# optronik.net
KiCad netlist of a schematic drawn in EAGLE
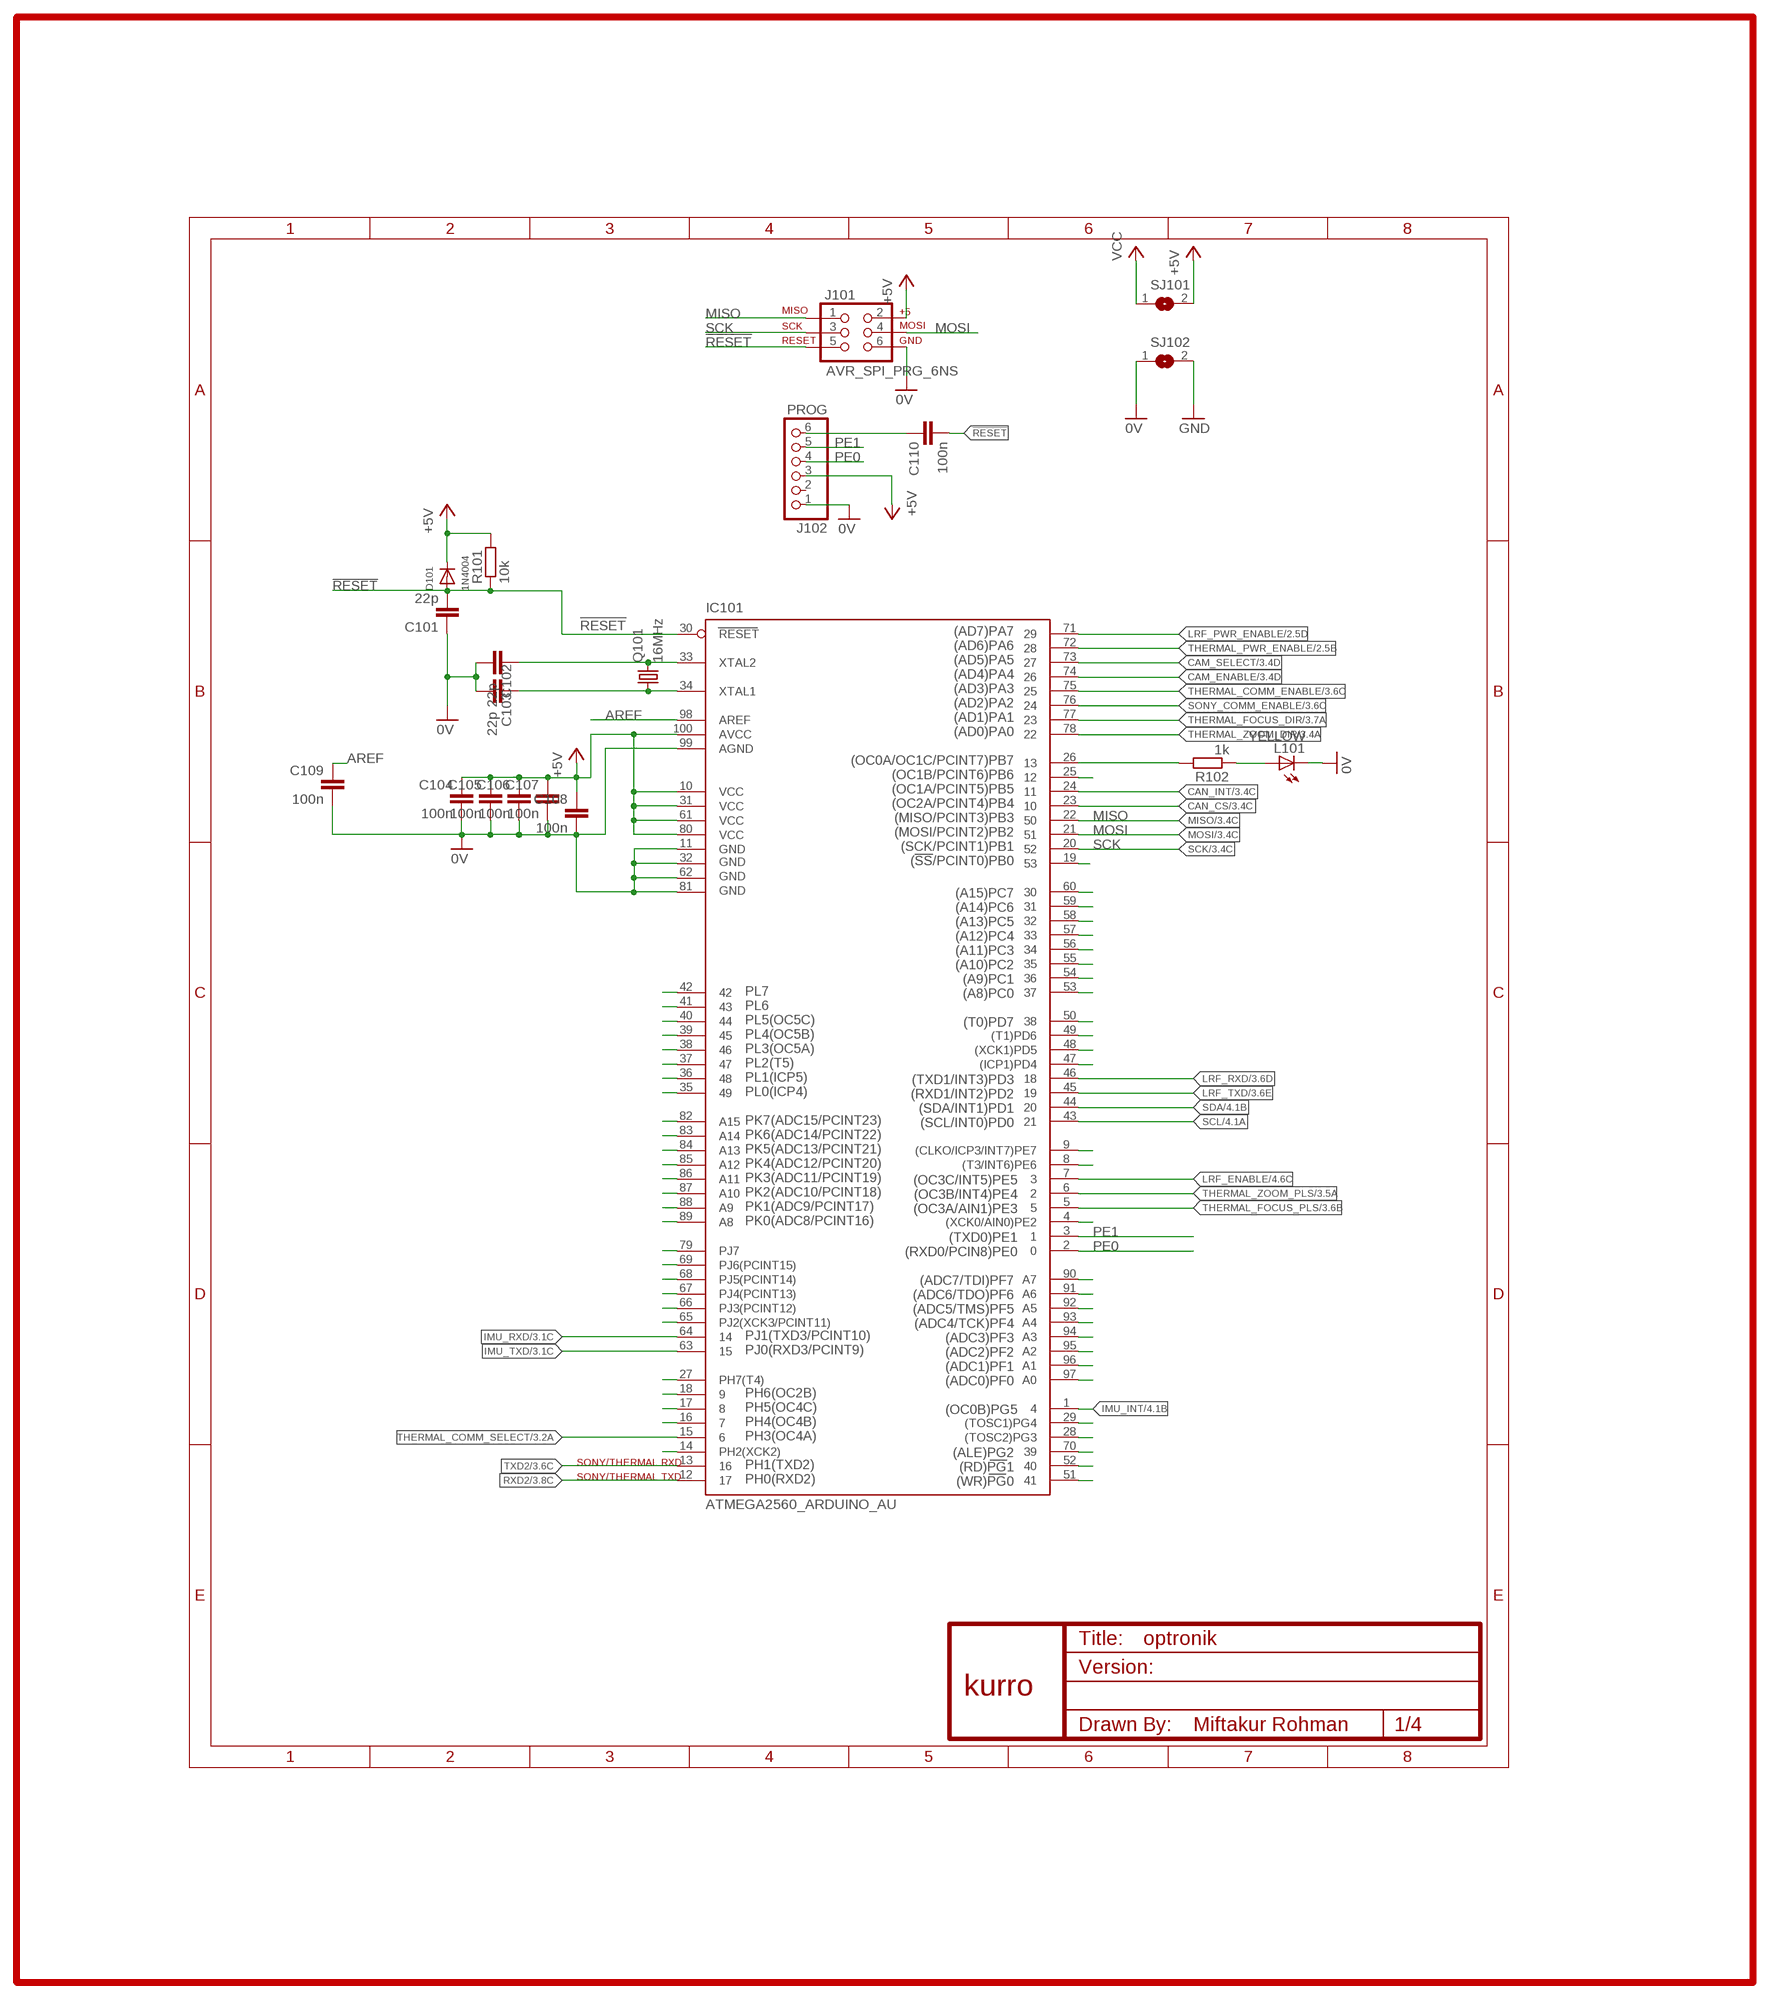
[diagram p0: schematic, sheet 1]
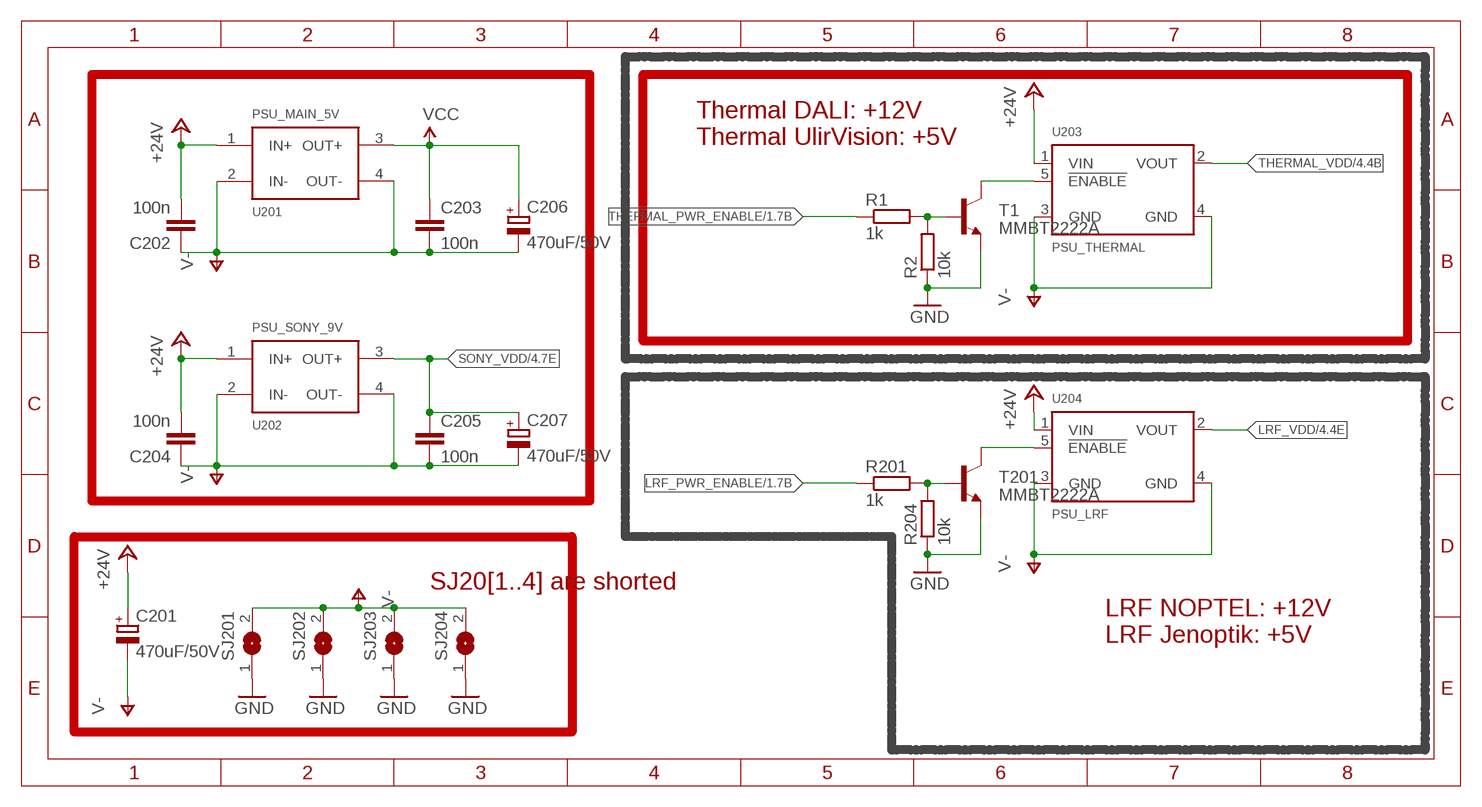
[diagram p1: schematic, sheet 2]
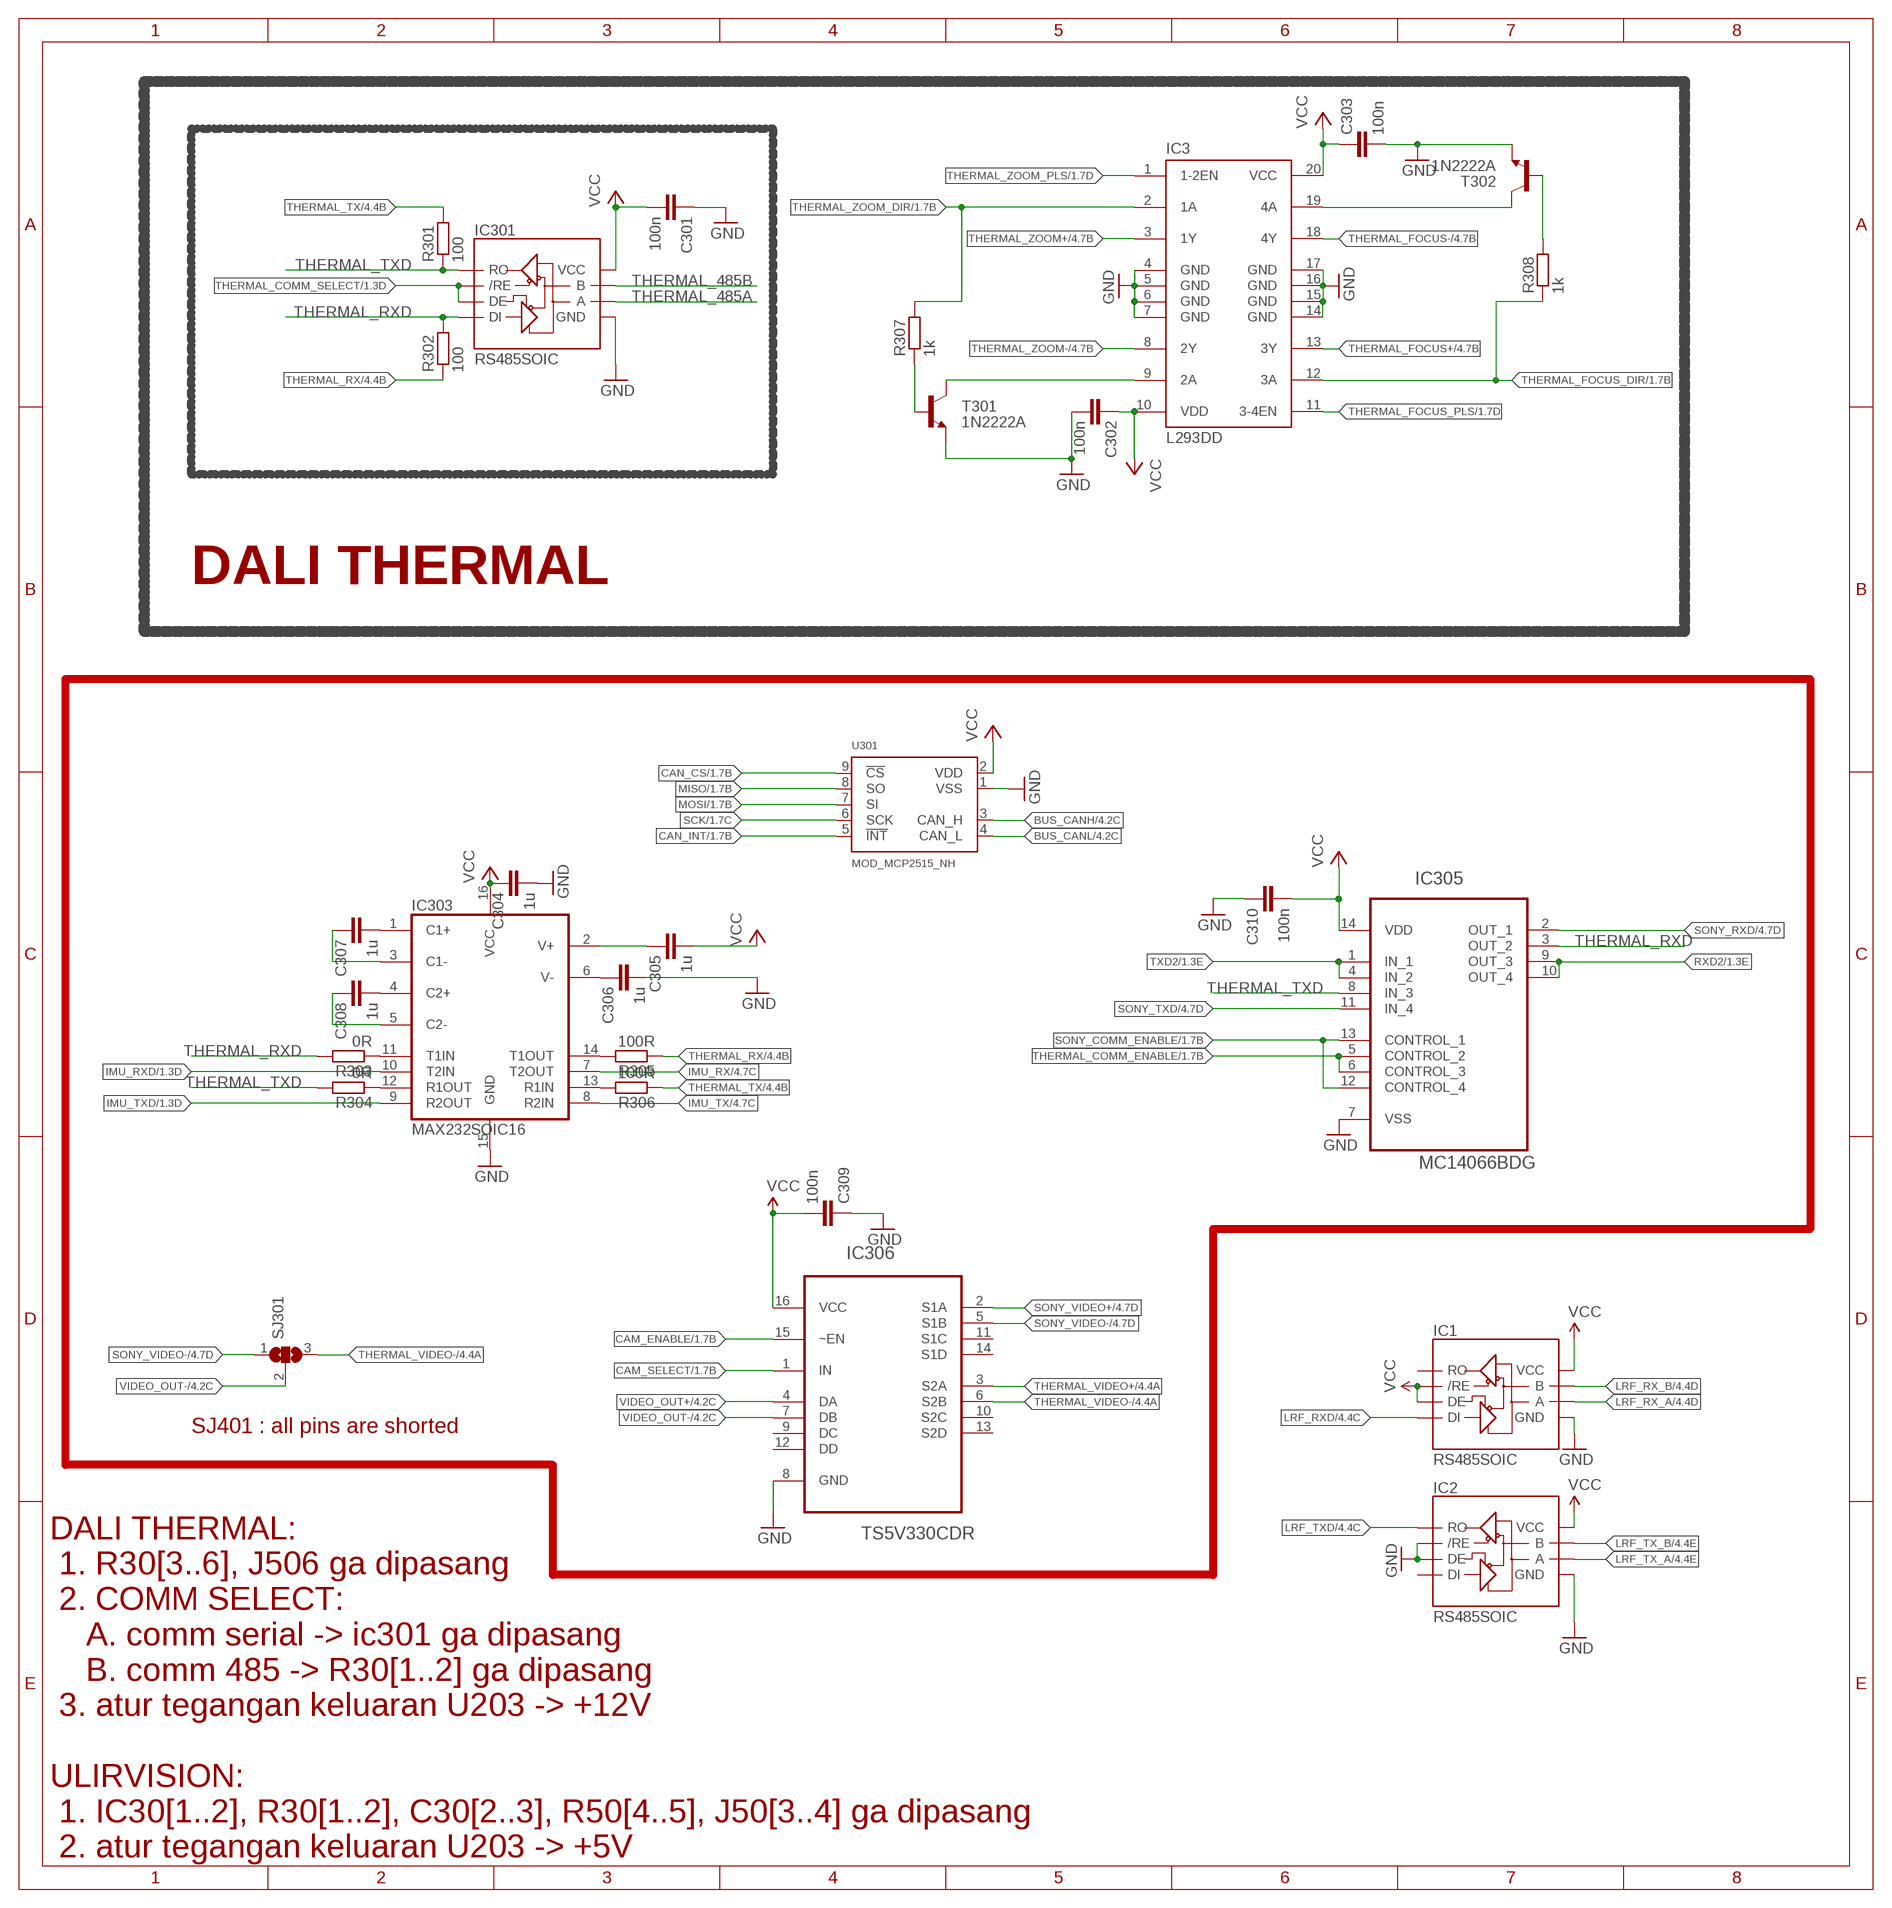
[diagram p2: schematic, sheet 3]
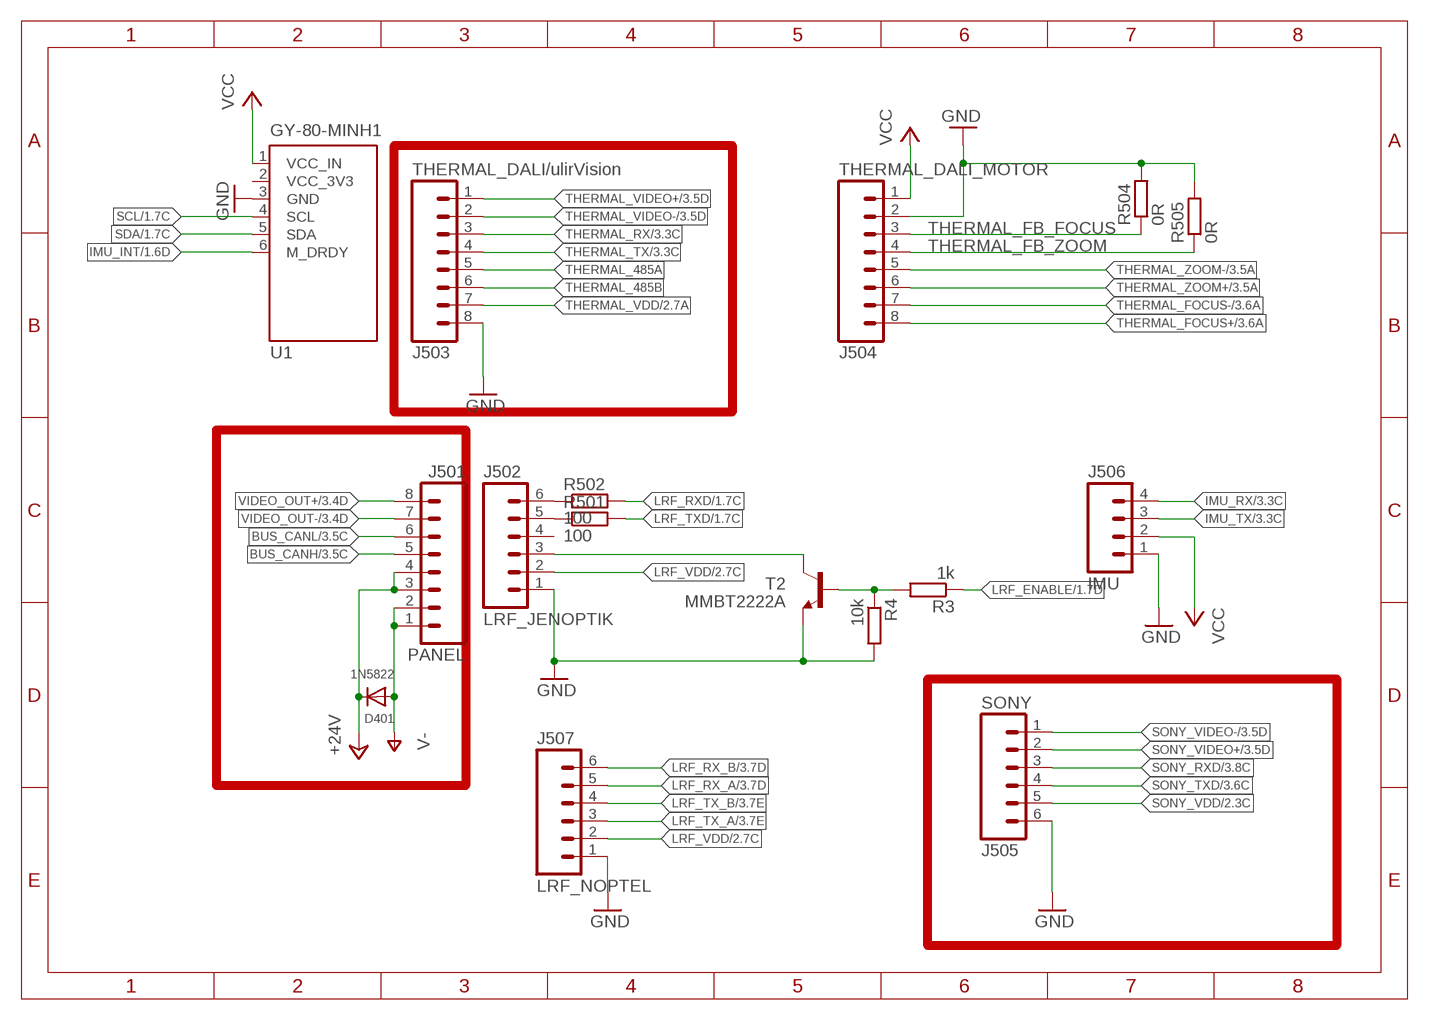
[diagram p3: schematic, sheet 4]

(export (version "E")
  (design (tool "Eeschema 10.0.6"))
  (components
    (comp (ref "D401")
      (value "1N5822")
      (footprint "eagle-import:SMADIODE")
      (libsource (lib "eagle-import") (part "DIODESMA"))
    )
    (comp (ref "J501")
      (value "PANEL")
      (footprint "eagle-import:XH-8-RA")
      (libsource (lib "eagle-import") (part "M08-XH-RA"))
    )
    (comp (ref "J502")
      (value "LRF_JENOPTIK")
      (footprint "eagle-import:XH-6-RA")
      (libsource (lib "eagle-import") (part "M06-XH-RA"))
    )
    (comp (ref "J503")
      (value "THERMAL_DALI/ulirVision")
      (footprint "eagle-import:XH-8-RA")
      (libsource (lib "eagle-import") (part "M08-XH-RA"))
    )
    (comp (ref "J504")
      (value "THERMAL_DALI_MOTOR")
      (footprint "eagle-import:XH-8-RA")
      (libsource (lib "eagle-import") (part "M08-XH-RA"))
    )
    (comp (ref "J505")
      (value "SONY")
      (footprint "eagle-import:XH-6-RA")
      (libsource (lib "eagle-import") (part "M06-XH-RA"))
    )
    (comp (ref "J506")
      (value "IMU")
      (footprint "eagle-import:XH-4-RA")
      (libsource (lib "eagle-import") (part "M04-XH-RA"))
    )
    (comp (ref "J507")
      (value "LRF_NOPTEL")
      (footprint "eagle-import:XH-6-RA")
      (libsource (lib "eagle-import") (part "M06-XH-RA"))
    )
    (comp (ref "R3")
      (value "1k")
      (footprint "eagle-import:R0603")
      (libsource (lib "eagle-import") (part "resistor_R-EU_R0603"))
    )
    (comp (ref "R4")
      (value "10k")
      (footprint "eagle-import:R0603")
      (libsource (lib "eagle-import") (part "resistor_R-EU_R0603"))
    )
    (comp (ref "R501")
      (value "100")
      (footprint "eagle-import:R0603")
      (libsource (lib "eagle-import") (part "R-EU_R0603"))
    )
    (comp (ref "R502")
      (value "100")
      (footprint "eagle-import:R0603")
      (libsource (lib "eagle-import") (part "R-EU_R0603"))
    )
    (comp (ref "R504")
      (value "0R")
      (footprint "eagle-import:R0603")
      (libsource (lib "eagle-import") (part "R-EU_R0603"))
    )
    (comp (ref "R505")
      (value "0R")
      (footprint "eagle-import:R0603")
      (libsource (lib "eagle-import") (part "R-EU_R0603"))
    )
    (comp (ref "T2")
      (value "MMBT2222A")
      (footprint "eagle-import:SOT23")
      (libsource (lib "eagle-import") (part "TRANSISTOR_NPNSOT23"))
    )
    (comp (ref "U1")
      (value "GY-80-MINH1")
      (footprint "eagle-import:GY-80-MINH1")
      (libsource (lib "eagle-import") (part "GY-80-MINH1"))
    )
    (comp (ref "C301")
      (value "100n")
      (footprint "eagle-import:C0603")
      (libsource (lib "eagle-import") (part "resistor_C-EUC0603"))
    )
    (comp (ref "C302")
      (value "100n")
      (footprint "eagle-import:C0603")
      (libsource (lib "eagle-import") (part "resistor_C-EUC0603"))
    )
    (comp (ref "C303")
      (value "100n")
      (footprint "eagle-import:C0603")
      (libsource (lib "eagle-import") (part "resistor_C-EUC0603"))
    )
    (comp (ref "C304")
      (value "1u")
      (footprint "eagle-import:C0603")
      (libsource (lib "eagle-import") (part "resistor_C-EUC0603"))
    )
    (comp (ref "C305")
      (value "1u")
      (footprint "eagle-import:C0603")
      (libsource (lib "eagle-import") (part "resistor_C-EUC0603"))
    )
    (comp (ref "C306")
      (value "1u")
      (footprint "eagle-import:C0603")
      (libsource (lib "eagle-import") (part "resistor_C-EUC0603"))
    )
    (comp (ref "C307")
      (value "1u")
      (footprint "eagle-import:C0603")
      (libsource (lib "eagle-import") (part "resistor_C-EUC0603"))
    )
    (comp (ref "C308")
      (value "1u")
      (footprint "eagle-import:C0603")
      (libsource (lib "eagle-import") (part "resistor_C-EUC0603"))
    )
    (comp (ref "C309")
      (value "100n")
      (footprint "eagle-import:C0603")
      (libsource (lib "eagle-import") (part "resistor_C-EUC0603"))
    )
    (comp (ref "C310")
      (value "100n")
      (footprint "eagle-import:C0603")
      (libsource (lib "eagle-import") (part "resistor_C-EUC0603"))
    )
    (comp (ref "IC1")
      (value "RS485SOIC")
      (footprint "eagle-import:SO08")
      (libsource (lib "eagle-import") (part "RS485SOIC"))
    )
    (comp (ref "IC2")
      (value "RS485SOIC")
      (footprint "eagle-import:SO08")
      (libsource (lib "eagle-import") (part "RS485SOIC"))
    )
    (comp (ref "IC3")
      (value "L293DD")
      (footprint "eagle-import:SO20W")
      (libsource (lib "eagle-import") (part "L293DD"))
    )
    (comp (ref "IC301")
      (value "RS485SOIC")
      (footprint "eagle-import:SO08")
      (libsource (lib "eagle-import") (part "RS485SOIC"))
    )
    (comp (ref "IC303")
      (value "MAX232SOIC16")
      (footprint "eagle-import:SO016")
      (libsource (lib "eagle-import") (part "MAX232SOIC16"))
    )
    (comp (ref "IC305")
      (value "MC14066BDG")
      (footprint "eagle-import:SOIC127P600X175-14N")
      (libsource (lib "eagle-import") (part "MC14066BDG"))
    )
    (comp (ref "IC306")
      (value "TS5V330CDR")
      (footprint "eagle-import:SOIC127P600X175-16N")
      (libsource (lib "eagle-import") (part "TS5V330CDR"))
    )
    (comp (ref "R301")
      (value "100")
      (footprint "eagle-import:R0603")
      (libsource (lib "eagle-import") (part "resistor_R-EU_R0603"))
    )
    (comp (ref "R302")
      (value "100")
      (footprint "eagle-import:R0603")
      (libsource (lib "eagle-import") (part "resistor_R-EU_R0603"))
    )
    (comp (ref "R303")
      (value "0R")
      (footprint "eagle-import:R0603")
      (libsource (lib "eagle-import") (part "resistor_R-EU_R0603"))
    )
    (comp (ref "R304")
      (value "0R")
      (footprint "eagle-import:R0603")
      (libsource (lib "eagle-import") (part "resistor_R-EU_R0603"))
    )
    (comp (ref "R305")
      (value "100R")
      (footprint "eagle-import:R0603")
      (libsource (lib "eagle-import") (part "resistor_R-EU_R0603"))
    )
    (comp (ref "R306")
      (value "100R")
      (footprint "eagle-import:R0603")
      (libsource (lib "eagle-import") (part "resistor_R-EU_R0603"))
    )
    (comp (ref "R307")
      (value "1k")
      (footprint "eagle-import:R0603")
      (libsource (lib "eagle-import") (part "resistor_R-EU_R0603"))
    )
    (comp (ref "R308")
      (value "1k")
      (footprint "eagle-import:R0603")
      (libsource (lib "eagle-import") (part "resistor_R-EU_R0603"))
    )
    (comp (ref "SJ301")
      (value "SJ2WS")
      (footprint "eagle-import:SJ_2S")
      (libsource (lib "eagle-import") (part "SJ2WS"))
    )
    (comp (ref "T301")
      (value "1N2222A")
      (footprint "eagle-import:SOT23")
      (libsource (lib "eagle-import") (part "TRANSISTOR_NPNSOT23"))
    )
    (comp (ref "T302")
      (value "1N2222A")
      (footprint "eagle-import:SOT23")
      (libsource (lib "eagle-import") (part "TRANSISTOR_NPNSOT23"))
    )
    (comp (ref "U301")
      (value "MOD_MCP2515_NH")
      (footprint "eagle-import:MCP2515_CAN2")
      (libsource (lib "eagle-import") (part "MOD_MCP2515_NH"))
    )
    (comp (ref "C201")
      (value "470uF/50V")
      (footprint "eagle-import:E3,5-10")
      (libsource (lib "eagle-import") (part "CPOL-EUE3.5-10"))
    )
    (comp (ref "C202")
      (value "100n")
      (footprint "eagle-import:C0603")
      (libsource (lib "eagle-import") (part "C-EUC0603"))
    )
    (comp (ref "C203")
      (value "100n")
      (footprint "eagle-import:C0603")
      (libsource (lib "eagle-import") (part "C-EUC0603"))
    )
    (comp (ref "C204")
      (value "100n")
      (footprint "eagle-import:C0603")
      (libsource (lib "eagle-import") (part "C-EUC0603"))
    )
    (comp (ref "C205")
      (value "100n")
      (footprint "eagle-import:C0603")
      (libsource (lib "eagle-import") (part "C-EUC0603"))
    )
    (comp (ref "C206")
      (value "470uF/50V")
      (footprint "eagle-import:E3,5-10")
      (libsource (lib "eagle-import") (part "CPOL-EUE3.5-10"))
    )
    (comp (ref "C207")
      (value "470uF/50V")
      (footprint "eagle-import:E3,5-10")
      (libsource (lib "eagle-import") (part "CPOL-EUE3.5-10"))
    )
    (comp (ref "R1")
      (value "1k")
      (footprint "eagle-import:R0603")
      (libsource (lib "eagle-import") (part "resistor_R-EU_R0603"))
    )
    (comp (ref "R2")
      (value "10k")
      (footprint "eagle-import:R0603")
      (libsource (lib "eagle-import") (part "resistor_R-EU_R0603"))
    )
    (comp (ref "R201")
      (value "1k")
      (footprint "eagle-import:R0603")
      (libsource (lib "eagle-import") (part "resistor_R-EU_R0603"))
    )
    (comp (ref "R204")
      (value "10k")
      (footprint "eagle-import:R0603")
      (libsource (lib "eagle-import") (part "resistor_R-EU_R0603"))
    )
    (comp (ref "SJ201")
      (value "SJS")
      (footprint "eagle-import:SJS")
      (libsource (lib "eagle-import") (part "SJS"))
    )
    (comp (ref "SJ202")
      (value "SJS")
      (footprint "eagle-import:SJS")
      (libsource (lib "eagle-import") (part "SJS"))
    )
    (comp (ref "SJ203")
      (value "SJS")
      (footprint "eagle-import:SJS")
      (libsource (lib "eagle-import") (part "SJS"))
    )
    (comp (ref "SJ204")
      (value "SJS")
      (footprint "eagle-import:SJS")
      (libsource (lib "eagle-import") (part "SJS"))
    )
    (comp (ref "T1")
      (value "MMBT2222A")
      (footprint "eagle-import:SOT23")
      (libsource (lib "eagle-import") (part "TRANSISTOR_NPNSOT23"))
    )
    (comp (ref "T201")
      (value "MMBT2222A")
      (footprint "eagle-import:SOT23")
      (libsource (lib "eagle-import") (part "TRANSISTOR_NPNSOT23"))
    )
    (comp (ref "U201")
      (value "PSU_MAIN_5V")
      (footprint "eagle-import:MP1584_MIN")
      (libsource (lib "eagle-import") (part "MP1584_MIN"))
    )
    (comp (ref "U202")
      (value "PSU_SONY_9V")
      (footprint "eagle-import:MP1584_MIN")
      (libsource (lib "eagle-import") (part "MP1584_MIN"))
    )
    (comp (ref "U203")
      (value "PSU_THERMAL")
      (footprint "eagle-import:MOD_LM2596")
      (libsource (lib "eagle-import") (part "MOD_LM2596"))
    )
    (comp (ref "U204")
      (value "PSU_LRF")
      (footprint "eagle-import:MOD_LM2596")
      (libsource (lib "eagle-import") (part "MOD_LM2596"))
    )
    (comp (ref "C101")
      (value "22p")
      (footprint "eagle-import:C0603")
      (libsource (lib "eagle-import") (part "C-EUC0603"))
    )
    (comp (ref "C102")
      (value "22p")
      (footprint "eagle-import:C0603")
      (libsource (lib "eagle-import") (part "C-EUC0603"))
    )
    (comp (ref "C103")
      (value "22p")
      (footprint "eagle-import:C0603")
      (libsource (lib "eagle-import") (part "C-EUC0603"))
    )
    (comp (ref "C104")
      (value "100n")
      (footprint "eagle-import:C0603")
      (libsource (lib "eagle-import") (part "C-EUC0603"))
    )
    (comp (ref "C105")
      (value "100n")
      (footprint "eagle-import:C0603")
      (libsource (lib "eagle-import") (part "C-EUC0603"))
    )
    (comp (ref "C106")
      (value "100n")
      (footprint "eagle-import:C0603")
      (libsource (lib "eagle-import") (part "C-EUC0603"))
    )
    (comp (ref "C107")
      (value "100n")
      (footprint "eagle-import:C0603")
      (libsource (lib "eagle-import") (part "C-EUC0603"))
    )
    (comp (ref "C108")
      (value "100n")
      (footprint "eagle-import:C0603")
      (libsource (lib "eagle-import") (part "C-EUC0603"))
    )
    (comp (ref "C109")
      (value "100n")
      (footprint "eagle-import:C0603")
      (libsource (lib "eagle-import") (part "C-EUC0603"))
    )
    (comp (ref "C110")
      (value "100n")
      (footprint "eagle-import:C0603")
      (libsource (lib "eagle-import") (part "C-EUC0603"))
    )
    (comp (ref "D101")
      (value "1N4004")
      (footprint "eagle-import:SOD-323F")
      (libsource (lib "eagle-import") (part "DIODESOD-323F"))
    )
    (comp (ref "IC101")
      (value "ATMEGA2560_ARDUINO_AU")
      (footprint "eagle-import:TQFP-100-14X14MM")
      (libsource (lib "eagle-import") (part "ATMEGA2560_ARDUINO_AU"))
    )
    (comp (ref "J101")
      (value "AVR_SPI_PRG_6NS")
      (footprint "eagle-import:2X3-NS")
      (libsource (lib "eagle-import") (part "AVR_SPI_PRG_6NS"))
    )
    (comp (ref "J102")
      (value "PROG")
      (footprint "eagle-import:1X06")
      (libsource (lib "eagle-import") (part "PINHD-1X6"))
    )
    (comp (ref "L101")
      (value "YELLOW")
      (footprint "eagle-import:LED5MM")
      (libsource (lib "eagle-import") (part "LED5MM"))
    )
    (comp (ref "Q101")
      (value "16MHz")
      (footprint "eagle-import:CRYSTAL-TXC-7A2")
      (libsource (lib "eagle-import") (part "CRYSTAL-TXC-7A2"))
    )
    (comp (ref "R101")
      (value "10k")
      (footprint "eagle-import:R0603")
      (libsource (lib "eagle-import") (part "resistor_R-EU_R0603"))
    )
    (comp (ref "R102")
      (value "1k")
      (footprint "eagle-import:R0603")
      (libsource (lib "eagle-import") (part "resistor_R-EU_R0603"))
    )
    (comp (ref "SJ101")
      (value "SJS")
      (footprint "eagle-import:SJS")
      (libsource (lib "eagle-import") (part "SJS"))
    )
    (comp (ref "SJ102")
      (value "SJS")
      (footprint "eagle-import:SJS")
      (libsource (lib "eagle-import") (part "SJS"))
    )
    (comp (ref "U$1")
      (value "KURRO_FOOTPRINT")
      (footprint "eagle-import:KURRO-LOGO")
      (libsource (lib "eagle-import") (part "KURRO_FOOTPRINT"))
    )
  )
  (nets
    (net (code "1") (name "+5V") (class "Default")
      (node (ref "C104") (pin "1") (pinfunction "1_1") (pintype "passive"))
      (node (ref "C105") (pin "1") (pinfunction "1_1") (pintype "passive"))
      (node (ref "C106") (pin "1") (pinfunction "1_1") (pintype "passive"))
      (node (ref "C107") (pin "1") (pinfunction "1_1") (pintype "passive"))
      (node (ref "C108") (pin "1") (pinfunction "1_1") (pintype "passive"))
      (node (ref "D101") (pin "C") (pinfunction "C_C") (pintype "passive"))
      (node (ref "IC101") (pin "10") (pinfunction "VCC_10") (pintype "power_in"))
      (node (ref "IC101") (pin "100") (pinfunction "AVCC_100") (pintype "power_in"))
      (node (ref "IC101") (pin "31") (pinfunction "VCC1_31") (pintype "power_in"))
      (node (ref "IC101") (pin "61") (pinfunction "VCC2_61") (pintype "power_in"))
      (node (ref "IC101") (pin "80") (pinfunction "VCC3_80") (pintype "power_in"))
      (node (ref "J101") (pin "2") (pinfunction "2_2") (pintype "passive"))
      (node (ref "J102") (pin "3") (pinfunction "3_3") (pintype "passive"))
      (node (ref "R101") (pin "2") (pinfunction "2_2") (pintype "passive"))
      (node (ref "SJ101") (pin "2") (pinfunction "2_2") (pintype "passive"))
    )
    (net (code "2") (name "+24V") (class "Default")
      (node (ref "C201") (pin "+") (pinfunction "+_+") (pintype "passive"))
      (node (ref "C202") (pin "2") (pinfunction "2_2") (pintype "passive"))
      (node (ref "C204") (pin "2") (pinfunction "2_2") (pintype "passive"))
      (node (ref "D401") (pin "C") (pinfunction "C_C") (pintype "passive"))
      (node (ref "J501") (pin "3") (pinfunction "3_3") (pintype "passive"))
      (node (ref "J501") (pin "4") (pinfunction "4_4") (pintype "passive"))
      (node (ref "U201") (pin "1") (pinfunction "IN+_1") (pintype "input"))
      (node (ref "U202") (pin "1") (pinfunction "IN+_1") (pintype "input"))
      (node (ref "U203") (pin "1") (pinfunction "VIN_1") (pintype "power_in"))
      (node (ref "U204") (pin "1") (pinfunction "VIN_1") (pintype "power_in"))
    )
    (net (code "3") (name "0V") (class "Default")
      (node (ref "C101") (pin "1") (pinfunction "1_1") (pintype "passive"))
      (node (ref "C102") (pin "1") (pinfunction "1_1") (pintype "passive"))
      (node (ref "C103") (pin "1") (pinfunction "1_1") (pintype "passive"))
      (node (ref "C104") (pin "2") (pinfunction "2_2") (pintype "passive"))
      (node (ref "C105") (pin "2") (pinfunction "2_2") (pintype "passive"))
      (node (ref "C106") (pin "2") (pinfunction "2_2") (pintype "passive"))
      (node (ref "C107") (pin "2") (pinfunction "2_2") (pintype "passive"))
      (node (ref "C108") (pin "2") (pinfunction "2_2") (pintype "passive"))
      (node (ref "C109") (pin "2") (pinfunction "2_2") (pintype "passive"))
      (node (ref "IC101") (pin "11") (pinfunction "GND_11") (pintype "power_in"))
      (node (ref "IC101") (pin "32") (pinfunction "GND1_32") (pintype "power_in"))
      (node (ref "IC101") (pin "62") (pinfunction "GND2_62") (pintype "power_in"))
      (node (ref "IC101") (pin "81") (pinfunction "GND3_81") (pintype "power_in"))
      (node (ref "IC101") (pin "99") (pinfunction "AGND_99") (pintype "power_in"))
      (node (ref "J101") (pin "6") (pinfunction "6_6") (pintype "passive"))
      (node (ref "J102") (pin "1") (pinfunction "1_1") (pintype "passive"))
      (node (ref "L101") (pin "K") (pinfunction "C_K") (pintype "passive"))
      (node (ref "SJ102") (pin "1") (pinfunction "1_1") (pintype "passive"))
    )
    (net (code "4") (name "AREF") (class "Default")
      (node (ref "C109") (pin "1") (pinfunction "1_1") (pintype "passive"))
      (node (ref "IC101") (pin "98") (pinfunction "AREF_98") (pintype "bidirectional"))
    )
    (net (code "5") (name "BUS_CANH") (class "Default")
      (node (ref "J501") (pin "5") (pinfunction "5_5") (pintype "passive"))
      (node (ref "U301") (pin "3") (pinfunction "CAN_H_3") (pintype "bidirectional"))
    )
    (net (code "6") (name "BUS_CANL") (class "Default")
      (node (ref "J501") (pin "6") (pinfunction "6_6") (pintype "passive"))
      (node (ref "U301") (pin "4") (pinfunction "CAN_L_4") (pintype "bidirectional"))
    )
    (net (code "7") (name "CAM_ENABLE") (class "Default")
      (node (ref "IC101") (pin "74") (pinfunction "26_74") (pintype "bidirectional"))
      (node (ref "IC306") (pin "15") (pinfunction "~{EN}_15") (pintype "input"))
    )
    (net (code "8") (name "CAM_SELECT") (class "Default")
      (node (ref "IC101") (pin "73") (pinfunction "27_73") (pintype "bidirectional"))
      (node (ref "IC306") (pin "1") (pinfunction "IN_1") (pintype "input"))
    )
    (net (code "9") (name "CAN_CS") (class "Default")
      (node (ref "IC101") (pin "23") (pinfunction "10_23") (pintype "bidirectional"))
      (node (ref "U301") (pin "9") (pinfunction "~{CS}_9") (pintype "bidirectional"))
    )
    (net (code "10") (name "CAN_INT") (class "Default")
      (node (ref "IC101") (pin "24") (pinfunction "11_24") (pintype "bidirectional"))
      (node (ref "U301") (pin "5") (pinfunction "~{INT}_5") (pintype "bidirectional"))
    )
    (net (code "11") (name "GND") (class "Default")
      (node (ref "C301") (pin "1") (pinfunction "1_1") (pintype "passive"))
      (node (ref "C302") (pin "2") (pinfunction "2_2") (pintype "passive"))
      (node (ref "C303") (pin "2") (pinfunction "2_2") (pintype "passive"))
      (node (ref "C304") (pin "2") (pinfunction "2_2") (pintype "passive"))
      (node (ref "C306") (pin "2") (pinfunction "2_2") (pintype "passive"))
      (node (ref "C309") (pin "1") (pinfunction "1_1") (pintype "passive"))
      (node (ref "C310") (pin "1") (pinfunction "1_1") (pintype "passive"))
      (node (ref "IC1") (pin "5") (pinfunction "GND_5") (pintype "bidirectional"))
      (node (ref "IC2") (pin "2") (pinfunction "/RE_2") (pintype "bidirectional"))
      (node (ref "IC2") (pin "3") (pinfunction "DE_3") (pintype "bidirectional"))
      (node (ref "IC2") (pin "5") (pinfunction "GND_5") (pintype "bidirectional"))
      (node (ref "IC3") (pin "14") (pinfunction "GND_14") (pintype "power_in"))
      (node (ref "IC3") (pin "15") (pinfunction "GND_15") (pintype "bidirectional"))
      (node (ref "IC3") (pin "16") (pinfunction "GND_16") (pintype "bidirectional"))
      (node (ref "IC3") (pin "17") (pinfunction "GND_17") (pintype "power_in"))
      (node (ref "IC3") (pin "4") (pinfunction "GND_4") (pintype "power_in"))
      (node (ref "IC3") (pin "5") (pinfunction "GND_5") (pintype "bidirectional"))
      (node (ref "IC3") (pin "6") (pinfunction "GND_6") (pintype "bidirectional"))
      (node (ref "IC3") (pin "7") (pinfunction "GND_7") (pintype "power_in"))
      (node (ref "IC301") (pin "5") (pinfunction "GND_5") (pintype "bidirectional"))
      (node (ref "IC303") (pin "15") (pinfunction "GND_15") (pintype "bidirectional"))
      (node (ref "IC305") (pin "7") (pinfunction "VSS_7") (pintype "passive"))
      (node (ref "IC306") (pin "8") (pinfunction "GND_8") (pintype "passive"))
      (node (ref "J502") (pin "1") (pinfunction "1_1") (pintype "passive"))
      (node (ref "J503") (pin "8") (pinfunction "8_8") (pintype "passive"))
      (node (ref "J504") (pin "2") (pinfunction "2_2") (pintype "passive"))
      (node (ref "J505") (pin "6") (pinfunction "6_6") (pintype "passive"))
      (node (ref "J506") (pin "1") (pinfunction "1_1") (pintype "passive"))
      (node (ref "J507") (pin "1") (pinfunction "1_1") (pintype "passive"))
      (node (ref "R2") (pin "1") (pinfunction "1_1") (pintype "passive"))
      (node (ref "R204") (pin "1") (pinfunction "1_1") (pintype "passive"))
      (node (ref "R4") (pin "2") (pinfunction "2_2") (pintype "passive"))
      (node (ref "R504") (pin "2") (pinfunction "2_2") (pintype "passive"))
      (node (ref "R505") (pin "2") (pinfunction "2_2") (pintype "passive"))
      (node (ref "SJ102") (pin "2") (pinfunction "2_2") (pintype "passive"))
      (node (ref "SJ201") (pin "1") (pinfunction "1_1") (pintype "passive"))
      (node (ref "SJ202") (pin "1") (pinfunction "1_1") (pintype "passive"))
      (node (ref "SJ203") (pin "1") (pinfunction "1_1") (pintype "passive"))
      (node (ref "SJ204") (pin "1") (pinfunction "1_1") (pintype "passive"))
      (node (ref "T1") (pin "2") (pinfunction "E_2") (pintype "passive"))
      (node (ref "T2") (pin "2") (pinfunction "E_2") (pintype "passive"))
      (node (ref "T201") (pin "2") (pinfunction "E_2") (pintype "passive"))
      (node (ref "T301") (pin "2") (pinfunction "E_2") (pintype "passive"))
      (node (ref "T302") (pin "2") (pinfunction "E_2") (pintype "passive"))
      (node (ref "U1") (pin "3") (pinfunction "GND_3") (pintype "bidirectional"))
      (node (ref "U301") (pin "1") (pinfunction "VSS_1") (pintype "bidirectional"))
    )
    (net (code "12") (name "IMU_INT") (class "Default")
      (node (ref "IC101") (pin "1") (pinfunction "4_1") (pintype "bidirectional"))
      (node (ref "U1") (pin "6") (pinfunction "M_DRDY_6") (pintype "bidirectional"))
    )
    (net (code "13") (name "IMU_RX") (class "Default")
      (node (ref "IC303") (pin "7") (pinfunction "T2OUT_7") (pintype "output"))
      (node (ref "J506") (pin "4") (pinfunction "4_4") (pintype "passive"))
    )
    (net (code "14") (name "IMU_RXD") (class "Default")
      (node (ref "IC101") (pin "64") (pinfunction "14_64") (pintype "bidirectional"))
      (node (ref "IC303") (pin "10") (pinfunction "T2IN_10") (pintype "input"))
    )
    (net (code "15") (name "IMU_TX") (class "Default")
      (node (ref "IC303") (pin "8") (pinfunction "R2IN_8") (pintype "input"))
      (node (ref "J506") (pin "3") (pinfunction "3_3") (pintype "passive"))
    )
    (net (code "16") (name "IMU_TXD") (class "Default")
      (node (ref "IC101") (pin "63") (pinfunction "15_63") (pintype "bidirectional"))
      (node (ref "IC303") (pin "9") (pinfunction "R2OUT_9") (pintype "output"))
    )
    (net (code "17") (name "LRF_ENABLE") (class "Default")
      (node (ref "IC101") (pin "7") (pinfunction "3_7") (pintype "bidirectional"))
      (node (ref "R3") (pin "1") (pinfunction "1_1") (pintype "passive"))
    )
    (net (code "18") (name "LRF_PWR_ENABLE") (class "Default")
      (node (ref "IC101") (pin "71") (pinfunction "29_71") (pintype "bidirectional"))
      (node (ref "R201") (pin "1") (pinfunction "1_1") (pintype "passive"))
    )
    (net (code "19") (name "LRF_RXD") (class "Default")
      (node (ref "IC1") (pin "4") (pinfunction "DI_4") (pintype "bidirectional"))
      (node (ref "IC101") (pin "46") (pinfunction "18_46") (pintype "bidirectional"))
      (node (ref "R502") (pin "2") (pinfunction "2_2") (pintype "passive"))
    )
    (net (code "20") (name "LRF_RX_A") (class "Default")
      (node (ref "IC1") (pin "6") (pinfunction "A_6") (pintype "bidirectional"))
      (node (ref "J507") (pin "5") (pinfunction "5_5") (pintype "passive"))
    )
    (net (code "21") (name "LRF_RX_B") (class "Default")
      (node (ref "IC1") (pin "7") (pinfunction "B_7") (pintype "bidirectional"))
      (node (ref "J507") (pin "6") (pinfunction "6_6") (pintype "passive"))
    )
    (net (code "22") (name "LRF_TXD") (class "Default")
      (node (ref "IC101") (pin "45") (pinfunction "19_45") (pintype "bidirectional"))
      (node (ref "IC2") (pin "1") (pinfunction "RO_1") (pintype "bidirectional"))
      (node (ref "R501") (pin "2") (pinfunction "2_2") (pintype "passive"))
    )
    (net (code "23") (name "LRF_TX_A") (class "Default")
      (node (ref "IC2") (pin "6") (pinfunction "A_6") (pintype "bidirectional"))
      (node (ref "J507") (pin "3") (pinfunction "3_3") (pintype "passive"))
    )
    (net (code "24") (name "LRF_TX_B") (class "Default")
      (node (ref "IC2") (pin "7") (pinfunction "B_7") (pintype "bidirectional"))
      (node (ref "J507") (pin "4") (pinfunction "4_4") (pintype "passive"))
    )
    (net (code "25") (name "LRF_VDD") (class "Default")
      (node (ref "J502") (pin "2") (pinfunction "2_2") (pintype "passive"))
      (node (ref "J507") (pin "2") (pinfunction "2_2") (pintype "passive"))
      (node (ref "U204") (pin "2") (pinfunction "VOUT_2") (pintype "output"))
    )
    (net (code "26") (name "MISO") (class "Default")
      (node (ref "IC101") (pin "22") (pinfunction "50_22") (pintype "bidirectional"))
      (node (ref "J101") (pin "1") (pinfunction "1_1") (pintype "passive"))
      (node (ref "U301") (pin "8") (pinfunction "SO_8") (pintype "bidirectional"))
    )
    (net (code "27") (name "MOSI") (class "Default")
      (node (ref "IC101") (pin "21") (pinfunction "51_21") (pintype "bidirectional"))
      (node (ref "J101") (pin "4") (pinfunction "4_4") (pintype "passive"))
      (node (ref "U301") (pin "7") (pinfunction "SI_7") (pintype "bidirectional"))
    )
    (net (code "28") (name "Net-(C110-Pad1)") (class "Default")
      (node (ref "C110") (pin "1") (pinfunction "1_1") (pintype "passive"))
      (node (ref "J102") (pin "6") (pinfunction "6_6") (pintype "passive"))
    )
    (net (code "29") (name "Net-(IC3-2A)") (class "Default")
      (node (ref "IC3") (pin "9") (pinfunction "2A_9") (pintype "input"))
      (node (ref "T301") (pin "3") (pinfunction "C_3") (pintype "passive"))
    )
    (net (code "30") (name "Net-(IC3-4A)") (class "Default")
      (node (ref "IC3") (pin "19") (pinfunction "4A_19") (pintype "input"))
      (node (ref "T302") (pin "3") (pinfunction "C_3") (pintype "passive"))
    )
    (net (code "31") (name "Net-(IC101-13)") (class "Default")
      (node (ref "IC101") (pin "26") (pinfunction "13_26") (pintype "bidirectional"))
      (node (ref "R102") (pin "2") (pinfunction "2_2") (pintype "passive"))
    )
    (net (code "32") (name "Net-(IC101-XTAL1)") (class "Default")
      (node (ref "C103") (pin "2") (pinfunction "2_2") (pintype "passive"))
      (node (ref "IC101") (pin "34") (pinfunction "XTAL1_34") (pintype "input"))
      (node (ref "Q101") (pin "P$1") (pinfunction "1_P$1") (pintype "passive"))
    )
    (net (code "33") (name "Net-(IC101-XTAL2)") (class "Default")
      (node (ref "C102") (pin "2") (pinfunction "2_2") (pintype "passive"))
      (node (ref "IC101") (pin "33") (pinfunction "XTAL2_33") (pintype "output"))
      (node (ref "Q101") (pin "P$2") (pinfunction "2_P$2") (pintype "passive"))
    )
    (net (code "34") (name "Net-(IC303-C1+)") (class "Default")
      (node (ref "C307") (pin "2") (pinfunction "2_2") (pintype "passive"))
      (node (ref "IC303") (pin "1") (pinfunction "C1+_1") (pintype "bidirectional"))
    )
    (net (code "35") (name "Net-(IC303-C1-)") (class "Default")
      (node (ref "C307") (pin "1") (pinfunction "1_1") (pintype "passive"))
      (node (ref "IC303") (pin "3") (pinfunction "C1-_3") (pintype "bidirectional"))
    )
    (net (code "36") (name "Net-(IC303-C2+)") (class "Default")
      (node (ref "C308") (pin "2") (pinfunction "2_2") (pintype "passive"))
      (node (ref "IC303") (pin "4") (pinfunction "C2+_4") (pintype "bidirectional"))
    )
    (net (code "37") (name "Net-(IC303-C2-)") (class "Default")
      (node (ref "C308") (pin "1") (pinfunction "1_1") (pintype "passive"))
      (node (ref "IC303") (pin "5") (pinfunction "C2-_5") (pintype "bidirectional"))
    )
    (net (code "38") (name "Net-(IC303-R1IN)") (class "Default")
      (node (ref "IC303") (pin "13") (pinfunction "R1IN_13") (pintype "input"))
      (node (ref "R306") (pin "2") (pinfunction "2_2") (pintype "passive"))
    )
    (net (code "39") (name "Net-(IC303-R1OUT)") (class "Default")
      (node (ref "IC303") (pin "12") (pinfunction "R1OUT_12") (pintype "output"))
      (node (ref "R304") (pin "1") (pinfunction "1_1") (pintype "passive"))
    )
    (net (code "40") (name "Net-(IC303-T1IN)") (class "Default")
      (node (ref "IC303") (pin "11") (pinfunction "T1IN_11") (pintype "input"))
      (node (ref "R303") (pin "1") (pinfunction "1_1") (pintype "passive"))
    )
    (net (code "41") (name "Net-(IC303-T1OUT)") (class "Default")
      (node (ref "IC303") (pin "14") (pinfunction "T1OUT_14") (pintype "output"))
      (node (ref "R305") (pin "2") (pinfunction "2_2") (pintype "passive"))
    )
    (net (code "42") (name "Net-(IC303-V+)") (class "Default")
      (node (ref "C305") (pin "1") (pinfunction "1_1") (pintype "passive"))
      (node (ref "IC303") (pin "2") (pinfunction "V+_2") (pintype "bidirectional"))
    )
    (net (code "43") (name "Net-(IC303-V-)") (class "Default")
      (node (ref "C306") (pin "1") (pinfunction "1_1") (pintype "passive"))
      (node (ref "IC303") (pin "6") (pinfunction "V-_6") (pintype "bidirectional"))
    )
    (net (code "44") (name "Net-(J502-Pad5)") (class "Default")
      (node (ref "J502") (pin "5") (pinfunction "5_5") (pintype "passive"))
      (node (ref "R501") (pin "1") (pinfunction "1_1") (pintype "passive"))
    )
    (net (code "45") (name "Net-(J502-Pad6)") (class "Default")
      (node (ref "J502") (pin "6") (pinfunction "6_6") (pintype "passive"))
      (node (ref "R502") (pin "1") (pinfunction "1_1") (pintype "passive"))
    )
    (net (code "46") (name "Net-(L101-PadA)") (class "Default")
      (node (ref "L101") (pin "A") (pinfunction "A_A") (pintype "passive"))
      (node (ref "R102") (pin "1") (pinfunction "1_1") (pintype "passive"))
    )
    (net (code "47") (name "Net-(T1-B)") (class "Default")
      (node (ref "R1") (pin "2") (pinfunction "2_2") (pintype "passive"))
      (node (ref "R2") (pin "2") (pinfunction "2_2") (pintype "passive"))
      (node (ref "T1") (pin "1") (pinfunction "B_1") (pintype "passive"))
    )
    (net (code "48") (name "Net-(T1-C)") (class "Default")
      (node (ref "T1") (pin "3") (pinfunction "C_3") (pintype "passive"))
      (node (ref "U203") (pin "5") (pinfunction "~{ENABLE}_5") (pintype "input"))
    )
    (net (code "49") (name "Net-(T2-B)") (class "Default")
      (node (ref "R3") (pin "2") (pinfunction "2_2") (pintype "passive"))
      (node (ref "R4") (pin "1") (pinfunction "1_1") (pintype "passive"))
      (node (ref "T2") (pin "1") (pinfunction "B_1") (pintype "passive"))
    )
    (net (code "50") (name "Net-(T2-C)") (class "Default")
      (node (ref "J502") (pin "3") (pinfunction "3_3") (pintype "passive"))
      (node (ref "T2") (pin "3") (pinfunction "C_3") (pintype "passive"))
    )
    (net (code "51") (name "Net-(T201-B)") (class "Default")
      (node (ref "R201") (pin "2") (pinfunction "2_2") (pintype "passive"))
      (node (ref "R204") (pin "2") (pinfunction "2_2") (pintype "passive"))
      (node (ref "T201") (pin "1") (pinfunction "B_1") (pintype "passive"))
    )
    (net (code "52") (name "Net-(T201-C)") (class "Default")
      (node (ref "T201") (pin "3") (pinfunction "C_3") (pintype "passive"))
      (node (ref "U204") (pin "5") (pinfunction "~{ENABLE}_5") (pintype "input"))
    )
    (net (code "53") (name "Net-(T301-B)") (class "Default")
      (node (ref "R307") (pin "1") (pinfunction "1_1") (pintype "passive"))
      (node (ref "T301") (pin "1") (pinfunction "B_1") (pintype "passive"))
    )
    (net (code "54") (name "Net-(T302-B)") (class "Default")
      (node (ref "R308") (pin "2") (pinfunction "2_2") (pintype "passive"))
      (node (ref "T302") (pin "1") (pinfunction "B_1") (pintype "passive"))
    )
    (net (code "55") (name "PE0") (class "Default")
      (node (ref "IC101") (pin "2") (pinfunction "0_2") (pintype "bidirectional"))
      (node (ref "J102") (pin "4") (pinfunction "4_4") (pintype "passive"))
    )
    (net (code "56") (name "PE1") (class "Default")
      (node (ref "IC101") (pin "3") (pinfunction "1_3") (pintype "bidirectional"))
      (node (ref "J102") (pin "5") (pinfunction "5_5") (pintype "passive"))
    )
    (net (code "57") (name "RXD2") (class "Default")
      (node (ref "IC101") (pin "12") (pinfunction "17_12") (pintype "bidirectional"))
      (node (ref "IC305") (pin "10") (pinfunction "OUT_4_10") (pintype "output"))
      (node (ref "IC305") (pin "9") (pinfunction "OUT_3_9") (pintype "output"))
    )
    (net (code "58") (name "SCK") (class "Default")
      (node (ref "IC101") (pin "20") (pinfunction "52_20") (pintype "bidirectional"))
      (node (ref "J101") (pin "3") (pinfunction "3_3") (pintype "passive"))
      (node (ref "U301") (pin "6") (pinfunction "SCK_6") (pintype "bidirectional"))
    )
    (net (code "59") (name "SCL") (class "Default")
      (node (ref "IC101") (pin "43") (pinfunction "21_43") (pintype "bidirectional"))
      (node (ref "U1") (pin "4") (pinfunction "SCL_4") (pintype "bidirectional"))
    )
    (net (code "60") (name "SDA") (class "Default")
      (node (ref "IC101") (pin "44") (pinfunction "20_44") (pintype "bidirectional"))
      (node (ref "U1") (pin "5") (pinfunction "SDA_5") (pintype "bidirectional"))
    )
    (net (code "61") (name "SONY_COMM_ENABLE") (class "Default")
      (node (ref "IC101") (pin "76") (pinfunction "24_76") (pintype "bidirectional"))
      (node (ref "IC305") (pin "12") (pinfunction "CONTROL_4_12") (pintype "input"))
      (node (ref "IC305") (pin "13") (pinfunction "CONTROL_1_13") (pintype "input"))
    )
    (net (code "62") (name "SONY_RXD") (class "Default")
      (node (ref "IC305") (pin "2") (pinfunction "OUT_1_2") (pintype "output"))
      (node (ref "J505") (pin "3") (pinfunction "3_3") (pintype "passive"))
    )
    (net (code "63") (name "SONY_TXD") (class "Default")
      (node (ref "IC305") (pin "11") (pinfunction "IN_4_11") (pintype "input"))
      (node (ref "J505") (pin "4") (pinfunction "4_4") (pintype "passive"))
    )
    (net (code "64") (name "SONY_VDD") (class "Default")
      (node (ref "C205") (pin "1") (pinfunction "1_1") (pintype "passive"))
      (node (ref "C207") (pin "+") (pinfunction "+_+") (pintype "passive"))
      (node (ref "J505") (pin "5") (pinfunction "5_5") (pintype "passive"))
      (node (ref "U202") (pin "3") (pinfunction "OUT+_3") (pintype "passive"))
    )
    (net (code "65") (name "SONY_VIDEO+") (class "Default")
      (node (ref "IC306") (pin "2") (pinfunction "S1A_2") (pintype "bidirectional"))
      (node (ref "J505") (pin "2") (pinfunction "2_2") (pintype "passive"))
    )
    (net (code "66") (name "SONY_VIDEO-") (class "Default")
      (node (ref "IC306") (pin "5") (pinfunction "S1B_5") (pintype "bidirectional"))
      (node (ref "J505") (pin "1") (pinfunction "1_1") (pintype "passive"))
      (node (ref "SJ301") (pin "1") (pinfunction "1_1") (pintype "passive"))
    )
    (net (code "67") (name "THERMAL_485A") (class "Default")
      (node (ref "IC301") (pin "6") (pinfunction "A_6") (pintype "bidirectional"))
      (node (ref "J503") (pin "5") (pinfunction "5_5") (pintype "passive"))
    )
    (net (code "68") (name "THERMAL_485B") (class "Default")
      (node (ref "IC301") (pin "7") (pinfunction "B_7") (pintype "bidirectional"))
      (node (ref "J503") (pin "6") (pinfunction "6_6") (pintype "passive"))
    )
    (net (code "69") (name "THERMAL_COMM_ENABLE") (class "Default")
      (node (ref "IC101") (pin "75") (pinfunction "25_75") (pintype "bidirectional"))
      (node (ref "IC305") (pin "5") (pinfunction "CONTROL_2_5") (pintype "input"))
      (node (ref "IC305") (pin "6") (pinfunction "CONTROL_3_6") (pintype "input"))
    )
    (net (code "70") (name "THERMAL_COMM_SELECT") (class "Default")
      (node (ref "IC101") (pin "15") (pinfunction "6_15") (pintype "bidirectional"))
      (node (ref "IC301") (pin "2") (pinfunction "/RE_2") (pintype "bidirectional"))
      (node (ref "IC301") (pin "3") (pinfunction "DE_3") (pintype "bidirectional"))
    )
    (net (code "71") (name "THERMAL_FB_FOCUS") (class "Default")
      (node (ref "J504") (pin "3") (pinfunction "3_3") (pintype "passive"))
      (node (ref "R504") (pin "1") (pinfunction "1_1") (pintype "passive"))
    )
    (net (code "72") (name "THERMAL_FB_ZOOM") (class "Default")
      (node (ref "J504") (pin "4") (pinfunction "4_4") (pintype "passive"))
      (node (ref "R505") (pin "1") (pinfunction "1_1") (pintype "passive"))
    )
    (net (code "73") (name "THERMAL_FOCUS+") (class "Default")
      (node (ref "IC3") (pin "13") (pinfunction "3Y_13") (pintype "output"))
      (node (ref "J504") (pin "8") (pinfunction "8_8") (pintype "passive"))
    )
    (net (code "74") (name "THERMAL_FOCUS-") (class "Default")
      (node (ref "IC3") (pin "18") (pinfunction "4Y_18") (pintype "output"))
      (node (ref "J504") (pin "7") (pinfunction "7_7") (pintype "passive"))
    )
    (net (code "75") (name "THERMAL_FOCUS_DIR") (class "Default")
      (node (ref "IC101") (pin "77") (pinfunction "23_77") (pintype "bidirectional"))
      (node (ref "IC3") (pin "12") (pinfunction "3A_12") (pintype "input"))
      (node (ref "R308") (pin "1") (pinfunction "1_1") (pintype "passive"))
    )
    (net (code "76") (name "THERMAL_FOCUS_PLS") (class "Default")
      (node (ref "IC101") (pin "5") (pinfunction "5_5") (pintype "bidirectional"))
      (node (ref "IC3") (pin "11") (pinfunction "3-4EN_11") (pintype "input"))
    )
    (net (code "77") (name "THERMAL_PWR_ENABLE") (class "Default")
      (node (ref "IC101") (pin "72") (pinfunction "28_72") (pintype "bidirectional"))
      (node (ref "R1") (pin "1") (pinfunction "1_1") (pintype "passive"))
    )
    (net (code "78") (name "THERMAL_RX") (class "Default")
      (node (ref "J503") (pin "3") (pinfunction "3_3") (pintype "passive"))
      (node (ref "R302") (pin "1") (pinfunction "1_1") (pintype "passive"))
      (node (ref "R305") (pin "1") (pinfunction "1_1") (pintype "passive"))
    )
    (net (code "79") (name "THERMAL_RXD") (class "Default")
      (node (ref "IC301") (pin "4") (pinfunction "DI_4") (pintype "bidirectional"))
      (node (ref "IC305") (pin "3") (pinfunction "OUT_2_3") (pintype "output"))
      (node (ref "R302") (pin "2") (pinfunction "2_2") (pintype "passive"))
      (node (ref "R303") (pin "2") (pinfunction "2_2") (pintype "passive"))
    )
    (net (code "80") (name "THERMAL_TX") (class "Default")
      (node (ref "J503") (pin "4") (pinfunction "4_4") (pintype "passive"))
      (node (ref "R301") (pin "2") (pinfunction "2_2") (pintype "passive"))
      (node (ref "R306") (pin "1") (pinfunction "1_1") (pintype "passive"))
    )
    (net (code "81") (name "THERMAL_TXD") (class "Default")
      (node (ref "IC301") (pin "1") (pinfunction "RO_1") (pintype "bidirectional"))
      (node (ref "IC305") (pin "8") (pinfunction "IN_3_8") (pintype "input"))
      (node (ref "R301") (pin "1") (pinfunction "1_1") (pintype "passive"))
      (node (ref "R304") (pin "2") (pinfunction "2_2") (pintype "passive"))
    )
    (net (code "82") (name "THERMAL_VDD") (class "Default")
      (node (ref "J503") (pin "7") (pinfunction "7_7") (pintype "passive"))
      (node (ref "U203") (pin "2") (pinfunction "VOUT_2") (pintype "output"))
    )
    (net (code "83") (name "THERMAL_VIDEO+") (class "Default")
      (node (ref "IC306") (pin "3") (pinfunction "S2A_3") (pintype "bidirectional"))
      (node (ref "J503") (pin "1") (pinfunction "1_1") (pintype "passive"))
    )
    (net (code "84") (name "THERMAL_VIDEO-") (class "Default")
      (node (ref "IC306") (pin "6") (pinfunction "S2B_6") (pintype "bidirectional"))
      (node (ref "J503") (pin "2") (pinfunction "2_2") (pintype "passive"))
      (node (ref "SJ301") (pin "3") (pinfunction "3_3") (pintype "passive"))
    )
    (net (code "85") (name "THERMAL_ZOOM+") (class "Default")
      (node (ref "IC3") (pin "3") (pinfunction "1Y_3") (pintype "output"))
      (node (ref "J504") (pin "6") (pinfunction "6_6") (pintype "passive"))
    )
    (net (code "86") (name "THERMAL_ZOOM-") (class "Default")
      (node (ref "IC3") (pin "8") (pinfunction "2Y_8") (pintype "output"))
      (node (ref "J504") (pin "5") (pinfunction "5_5") (pintype "passive"))
    )
    (net (code "87") (name "THERMAL_ZOOM_DIR") (class "Default")
      (node (ref "IC101") (pin "78") (pinfunction "22_78") (pintype "bidirectional"))
      (node (ref "IC3") (pin "2") (pinfunction "1A_2") (pintype "input"))
      (node (ref "R307") (pin "2") (pinfunction "2_2") (pintype "passive"))
    )
    (net (code "88") (name "THERMAL_ZOOM_PLS") (class "Default")
      (node (ref "IC101") (pin "6") (pinfunction "2_6") (pintype "bidirectional"))
      (node (ref "IC3") (pin "1") (pinfunction "1-2EN_1") (pintype "input"))
    )
    (net (code "89") (name "TXD2") (class "Default")
      (node (ref "IC101") (pin "13") (pinfunction "16_13") (pintype "bidirectional"))
      (node (ref "IC305") (pin "1") (pinfunction "IN_1_1") (pintype "input"))
      (node (ref "IC305") (pin "4") (pinfunction "IN_2_4") (pintype "input"))
    )
    (net (code "90") (name "V-") (class "Default")
      (node (ref "C201") (pin "-") (pinfunction "-_-") (pintype "passive"))
      (node (ref "C202") (pin "1") (pinfunction "1_1") (pintype "passive"))
      (node (ref "C203") (pin "2") (pinfunction "2_2") (pintype "passive"))
      (node (ref "C204") (pin "1") (pinfunction "1_1") (pintype "passive"))
      (node (ref "C205") (pin "2") (pinfunction "2_2") (pintype "passive"))
      (node (ref "C206") (pin "-") (pinfunction "-_-") (pintype "passive"))
      (node (ref "C207") (pin "-") (pinfunction "-_-") (pintype "passive"))
      (node (ref "D401") (pin "A") (pinfunction "A_A") (pintype "passive"))
      (node (ref "J501") (pin "1") (pinfunction "1_1") (pintype "passive"))
      (node (ref "J501") (pin "2") (pinfunction "2_2") (pintype "passive"))
      (node (ref "SJ201") (pin "2") (pinfunction "2_2") (pintype "passive"))
      (node (ref "SJ202") (pin "2") (pinfunction "2_2") (pintype "passive"))
      (node (ref "SJ203") (pin "2") (pinfunction "2_2") (pintype "passive"))
      (node (ref "SJ204") (pin "2") (pinfunction "2_2") (pintype "passive"))
      (node (ref "U201") (pin "2") (pinfunction "IN-_2") (pintype "passive"))
      (node (ref "U201") (pin "4") (pinfunction "OUT-_4") (pintype "passive"))
      (node (ref "U202") (pin "2") (pinfunction "IN-_2") (pintype "passive"))
      (node (ref "U202") (pin "4") (pinfunction "OUT-_4") (pintype "passive"))
      (node (ref "U203") (pin "3") (pinfunction "GND_3") (pintype "passive"))
      (node (ref "U203") (pin "4") (pinfunction "GND_4") (pintype "passive"))
      (node (ref "U204") (pin "3") (pinfunction "GND_3") (pintype "passive"))
      (node (ref "U204") (pin "4") (pinfunction "GND_4") (pintype "passive"))
    )
    (net (code "91") (name "VCC") (class "Default")
      (node (ref "C203") (pin "1") (pinfunction "1_1") (pintype "passive"))
      (node (ref "C206") (pin "+") (pinfunction "+_+") (pintype "passive"))
      (node (ref "C301") (pin "2") (pinfunction "2_2") (pintype "passive"))
      (node (ref "C302") (pin "1") (pinfunction "1_1") (pintype "passive"))
      (node (ref "C303") (pin "1") (pinfunction "1_1") (pintype "passive"))
      (node (ref "C304") (pin "1") (pinfunction "1_1") (pintype "passive"))
      (node (ref "C305") (pin "2") (pinfunction "2_2") (pintype "passive"))
      (node (ref "C309") (pin "2") (pinfunction "2_2") (pintype "passive"))
      (node (ref "C310") (pin "2") (pinfunction "2_2") (pintype "passive"))
      (node (ref "IC1") (pin "2") (pinfunction "/RE_2") (pintype "bidirectional"))
      (node (ref "IC1") (pin "3") (pinfunction "DE_3") (pintype "bidirectional"))
      (node (ref "IC1") (pin "8") (pinfunction "VCC_8") (pintype "bidirectional"))
      (node (ref "IC2") (pin "8") (pinfunction "VCC_8") (pintype "bidirectional"))
      (node (ref "IC3") (pin "10") (pinfunction "VDD_10") (pintype "power_in"))
      (node (ref "IC3") (pin "20") (pinfunction "VCC_20") (pintype "power_in"))
      (node (ref "IC301") (pin "8") (pinfunction "VCC_8") (pintype "bidirectional"))
      (node (ref "IC303") (pin "16") (pinfunction "VCC_16") (pintype "bidirectional"))
      (node (ref "IC305") (pin "14") (pinfunction "VDD_14") (pintype "power_in"))
      (node (ref "IC306") (pin "16") (pinfunction "VCC_16") (pintype "power_in"))
      (node (ref "J504") (pin "1") (pinfunction "1_1") (pintype "passive"))
      (node (ref "J506") (pin "2") (pinfunction "2_2") (pintype "passive"))
      (node (ref "SJ101") (pin "1") (pinfunction "1_1") (pintype "passive"))
      (node (ref "U1") (pin "1") (pinfunction "VCC_IN_1") (pintype "bidirectional"))
      (node (ref "U201") (pin "3") (pinfunction "OUT+_3") (pintype "passive"))
      (node (ref "U301") (pin "2") (pinfunction "VDD_2") (pintype "bidirectional"))
    )
    (net (code "92") (name "VIDEO_OUT+") (class "Default")
      (node (ref "IC306") (pin "4") (pinfunction "DA_4") (pintype "bidirectional"))
      (node (ref "J501") (pin "8") (pinfunction "8_8") (pintype "passive"))
    )
    (net (code "93") (name "VIDEO_OUT-") (class "Default")
      (node (ref "IC306") (pin "7") (pinfunction "DB_7") (pintype "bidirectional"))
      (node (ref "J501") (pin "7") (pinfunction "7_7") (pintype "passive"))
      (node (ref "SJ301") (pin "2") (pinfunction "2_2") (pintype "passive"))
    )
    (net (code "94") (name "unconnected-(IC1-RO-Pad1)") (class "Default")
      (node (ref "IC1") (pin "1") (pinfunction "RO_1") (pintype "bidirectional"))
    )
    (net (code "95") (name "unconnected-(IC2-DI-Pad4)") (class "Default")
      (node (ref "IC2") (pin "4") (pinfunction "DI_4") (pintype "bidirectional"))
    )
    (net (code "96") (name "unconnected-(IC101-(CLKO{slash}ICP3{slash}INT7)PE7-Pad9)") (class "Default")
      (node (ref "IC101") (pin "9") (pinfunction "(CLKO/ICP3/INT7)PE7_9") (pintype "bidirectional"))
    )
    (net (code "97") (name "unconnected-(IC101-(ICP1)PD4-Pad47)") (class "Default")
      (node (ref "IC101") (pin "47") (pinfunction "(ICP1)PD4_47") (pintype "bidirectional"))
    )
    (net (code "98") (name "unconnected-(IC101-(T1)PD6-Pad49)") (class "Default")
      (node (ref "IC101") (pin "49") (pinfunction "(T1)PD6_49") (pintype "bidirectional"))
    )
    (net (code "99") (name "unconnected-(IC101-(T3{slash}INT6)PE6-Pad8)") (class "Default")
      (node (ref "IC101") (pin "8") (pinfunction "(T3/INT6)PE6_8") (pintype "bidirectional"))
    )
    (net (code "100") (name "unconnected-(IC101-(TOSC1)PG4-Pad29)") (class "Default")
      (node (ref "IC101") (pin "29") (pinfunction "(TOSC1)PG4_29") (pintype "bidirectional"))
    )
    (net (code "101") (name "unconnected-(IC101-(TOSC2)PG3-Pad28)") (class "Default")
      (node (ref "IC101") (pin "28") (pinfunction "(TOSC2)PG3_28") (pintype "bidirectional"))
    )
    (net (code "102") (name "unconnected-(IC101-(XCK0{slash}AIN0)PE2-Pad4)") (class "Default")
      (node (ref "IC101") (pin "4") (pinfunction "(XCK0/AIN0)PE2_4") (pintype "bidirectional"))
    )
    (net (code "103") (name "unconnected-(IC101-(XCK1)PD5-Pad48)") (class "Default")
      (node (ref "IC101") (pin "48") (pinfunction "(XCK1)PD5_48") (pintype "bidirectional"))
    )
    (net (code "104") (name "unconnected-(IC101-7-Pad16)") (class "Default")
      (node (ref "IC101") (pin "16") (pinfunction "7_16") (pintype "bidirectional"))
    )
    (net (code "105") (name "unconnected-(IC101-8-Pad17)") (class "Default")
      (node (ref "IC101") (pin "17") (pinfunction "8_17") (pintype "bidirectional"))
    )
    (net (code "106") (name "unconnected-(IC101-9-Pad18)") (class "Default")
      (node (ref "IC101") (pin "18") (pinfunction "9_18") (pintype "bidirectional"))
    )
    (net (code "107") (name "unconnected-(IC101-12-Pad25)") (class "Default")
      (node (ref "IC101") (pin "25") (pinfunction "12_25") (pintype "bidirectional"))
    )
    (net (code "108") (name "unconnected-(IC101-30-Pad60)") (class "Default")
      (node (ref "IC101") (pin "60") (pinfunction "30_60") (pintype "bidirectional"))
    )
    (net (code "109") (name "unconnected-(IC101-31-Pad59)") (class "Default")
      (node (ref "IC101") (pin "59") (pinfunction "31_59") (pintype "bidirectional"))
    )
    (net (code "110") (name "unconnected-(IC101-32-Pad58)") (class "Default")
      (node (ref "IC101") (pin "58") (pinfunction "32_58") (pintype "bidirectional"))
    )
    (net (code "111") (name "unconnected-(IC101-33-Pad57)") (class "Default")
      (node (ref "IC101") (pin "57") (pinfunction "33_57") (pintype "bidirectional"))
    )
    (net (code "112") (name "unconnected-(IC101-34-Pad56)") (class "Default")
      (node (ref "IC101") (pin "56") (pinfunction "34_56") (pintype "bidirectional"))
    )
    (net (code "113") (name "unconnected-(IC101-35-Pad55)") (class "Default")
      (node (ref "IC101") (pin "55") (pinfunction "35_55") (pintype "bidirectional"))
    )
    (net (code "114") (name "unconnected-(IC101-36-Pad54)") (class "Default")
      (node (ref "IC101") (pin "54") (pinfunction "36_54") (pintype "bidirectional"))
    )
    (net (code "115") (name "unconnected-(IC101-37-Pad53)") (class "Default")
      (node (ref "IC101") (pin "53") (pinfunction "37_53") (pintype "bidirectional"))
    )
    (net (code "116") (name "unconnected-(IC101-38-Pad50)") (class "Default")
      (node (ref "IC101") (pin "50") (pinfunction "38_50") (pintype "bidirectional"))
    )
    (net (code "117") (name "unconnected-(IC101-39-Pad70)") (class "Default")
      (node (ref "IC101") (pin "70") (pinfunction "39_70") (pintype "bidirectional"))
    )
    (net (code "118") (name "unconnected-(IC101-40-Pad52)") (class "Default")
      (node (ref "IC101") (pin "52") (pinfunction "40_52") (pintype "bidirectional"))
    )
    (net (code "119") (name "unconnected-(IC101-41-Pad51)") (class "Default")
      (node (ref "IC101") (pin "51") (pinfunction "41_51") (pintype "bidirectional"))
    )
    (net (code "120") (name "unconnected-(IC101-43-Pad41)") (class "Default")
      (node (ref "IC101") (pin "41") (pinfunction "43_41") (pintype "bidirectional"))
    )
    (net (code "121") (name "unconnected-(IC101-44-Pad40)") (class "Default")
      (node (ref "IC101") (pin "40") (pinfunction "44_40") (pintype "bidirectional"))
    )
    (net (code "122") (name "unconnected-(IC101-45-Pad39)") (class "Default")
      (node (ref "IC101") (pin "39") (pinfunction "45_39") (pintype "bidirectional"))
    )
    (net (code "123") (name "unconnected-(IC101-46-Pad38)") (class "Default")
      (node (ref "IC101") (pin "38") (pinfunction "46_38") (pintype "bidirectional"))
    )
    (net (code "124") (name "unconnected-(IC101-47-Pad37)") (class "Default")
      (node (ref "IC101") (pin "37") (pinfunction "47_37") (pintype "bidirectional"))
    )
    (net (code "125") (name "unconnected-(IC101-48-Pad36)") (class "Default")
      (node (ref "IC101") (pin "36") (pinfunction "48_36") (pintype "bidirectional"))
    )
    (net (code "126") (name "unconnected-(IC101-49-Pad35)") (class "Default")
      (node (ref "IC101") (pin "35") (pinfunction "49_35") (pintype "bidirectional"))
    )
    (net (code "127") (name "unconnected-(IC101-53-Pad19)") (class "Default")
      (node (ref "IC101") (pin "19") (pinfunction "53_19") (pintype "bidirectional"))
    )
    (net (code "128") (name "unconnected-(IC101-A0-Pad97)") (class "Default")
      (node (ref "IC101") (pin "97") (pinfunction "A0_97") (pintype "bidirectional"))
    )
    (net (code "129") (name "unconnected-(IC101-A1-Pad96)") (class "Default")
      (node (ref "IC101") (pin "96") (pinfunction "A1_96") (pintype "bidirectional"))
    )
    (net (code "130") (name "unconnected-(IC101-A2-Pad95)") (class "Default")
      (node (ref "IC101") (pin "95") (pinfunction "A2_95") (pintype "bidirectional"))
    )
    (net (code "131") (name "unconnected-(IC101-A3-Pad94)") (class "Default")
      (node (ref "IC101") (pin "94") (pinfunction "A3_94") (pintype "bidirectional"))
    )
    (net (code "132") (name "unconnected-(IC101-A4-Pad93)") (class "Default")
      (node (ref "IC101") (pin "93") (pinfunction "A4_93") (pintype "bidirectional"))
    )
    (net (code "133") (name "unconnected-(IC101-A5-Pad92)") (class "Default")
      (node (ref "IC101") (pin "92") (pinfunction "A5_92") (pintype "bidirectional"))
    )
    (net (code "134") (name "unconnected-(IC101-A6-Pad91)") (class "Default")
      (node (ref "IC101") (pin "91") (pinfunction "A6_91") (pintype "bidirectional"))
    )
    (net (code "135") (name "unconnected-(IC101-A7-Pad90)") (class "Default")
      (node (ref "IC101") (pin "90") (pinfunction "A7_90") (pintype "bidirectional"))
    )
    (net (code "136") (name "unconnected-(IC101-A8-Pad89)") (class "Default")
      (node (ref "IC101") (pin "89") (pinfunction "A8_89") (pintype "bidirectional"))
    )
    (net (code "137") (name "unconnected-(IC101-A9-Pad88)") (class "Default")
      (node (ref "IC101") (pin "88") (pinfunction "A9_88") (pintype "bidirectional"))
    )
    (net (code "138") (name "unconnected-(IC101-A10-Pad87)") (class "Default")
      (node (ref "IC101") (pin "87") (pinfunction "A10_87") (pintype "bidirectional"))
    )
    (net (code "139") (name "unconnected-(IC101-A11-Pad86)") (class "Default")
      (node (ref "IC101") (pin "86") (pinfunction "A11_86") (pintype "bidirectional"))
    )
    (net (code "140") (name "unconnected-(IC101-A12-Pad85)") (class "Default")
      (node (ref "IC101") (pin "85") (pinfunction "A12_85") (pintype "bidirectional"))
    )
    (net (code "141") (name "unconnected-(IC101-A13-Pad84)") (class "Default")
      (node (ref "IC101") (pin "84") (pinfunction "A13_84") (pintype "bidirectional"))
    )
    (net (code "142") (name "unconnected-(IC101-A14-Pad83)") (class "Default")
      (node (ref "IC101") (pin "83") (pinfunction "A14_83") (pintype "bidirectional"))
    )
    (net (code "143") (name "unconnected-(IC101-A15-Pad82)") (class "Default")
      (node (ref "IC101") (pin "82") (pinfunction "A15_82") (pintype "bidirectional"))
    )
    (net (code "144") (name "unconnected-(IC101-PH2(XCK2)-Pad14)") (class "Default")
      (node (ref "IC101") (pin "14") (pinfunction "PH2(XCK2)_14") (pintype "bidirectional"))
    )
    (net (code "145") (name "unconnected-(IC101-PH7(T4)-Pad27)") (class "Default")
      (node (ref "IC101") (pin "27") (pinfunction "PH7(T4)_27") (pintype "bidirectional"))
    )
    (net (code "146") (name "unconnected-(IC101-PJ2(XCK3{slash}PCINT11)-Pad65)") (class "Default")
      (node (ref "IC101") (pin "65") (pinfunction "PJ2(XCK3/PCINT11)_65") (pintype "bidirectional"))
    )
    (net (code "147") (name "unconnected-(IC101-PJ3(PCINT12)-Pad66)") (class "Default")
      (node (ref "IC101") (pin "66") (pinfunction "PJ3(PCINT12)_66") (pintype "bidirectional"))
    )
    (net (code "148") (name "unconnected-(IC101-PJ4(PCINT13)-Pad67)") (class "Default")
      (node (ref "IC101") (pin "67") (pinfunction "PJ4(PCINT13)_67") (pintype "bidirectional"))
    )
    (net (code "149") (name "unconnected-(IC101-PJ5(PCINT14)-Pad68)") (class "Default")
      (node (ref "IC101") (pin "68") (pinfunction "PJ5(PCINT14)_68") (pintype "bidirectional"))
    )
    (net (code "150") (name "unconnected-(IC101-PJ6(PCINT15)-Pad69)") (class "Default")
      (node (ref "IC101") (pin "69") (pinfunction "PJ6(PCINT15)_69") (pintype "bidirectional"))
    )
    (net (code "151") (name "unconnected-(IC101-PJ7-Pad79)") (class "Default")
      (node (ref "IC101") (pin "79") (pinfunction "PJ7_79") (pintype "bidirectional"))
    )
    (net (code "152") (name "unconnected-(IC101-Pad42)") (class "Default")
      (node (ref "IC101") (pin "42") (pinfunction "42_42") (pintype "bidirectional"))
    )
    (net (code "153") (name "unconnected-(IC306-DC-Pad9)") (class "Default")
      (node (ref "IC306") (pin "9") (pinfunction "DC_9") (pintype "bidirectional"))
    )
    (net (code "154") (name "unconnected-(IC306-DD-Pad12)") (class "Default")
      (node (ref "IC306") (pin "12") (pinfunction "DD_12") (pintype "bidirectional"))
    )
    (net (code "155") (name "unconnected-(IC306-S1C-Pad11)") (class "Default")
      (node (ref "IC306") (pin "11") (pinfunction "S1C_11") (pintype "bidirectional"))
    )
    (net (code "156") (name "unconnected-(IC306-S1D-Pad14)") (class "Default")
      (node (ref "IC306") (pin "14") (pinfunction "S1D_14") (pintype "bidirectional"))
    )
    (net (code "157") (name "unconnected-(IC306-S2C-Pad10)") (class "Default")
      (node (ref "IC306") (pin "10") (pinfunction "S2C_10") (pintype "bidirectional"))
    )
    (net (code "158") (name "unconnected-(IC306-S2D-Pad13)") (class "Default")
      (node (ref "IC306") (pin "13") (pinfunction "S2D_13") (pintype "bidirectional"))
    )
    (net (code "159") (name "unconnected-(J102-Pad2)") (class "Default")
      (node (ref "J102") (pin "2") (pinfunction "2_2") (pintype "passive"))
    )
    (net (code "160") (name "unconnected-(J502-Pad4)") (class "Default")
      (node (ref "J502") (pin "4") (pinfunction "4_4") (pintype "passive"))
    )
    (net (code "161") (name "unconnected-(U1-VCC_3V3-Pad2)") (class "Default")
      (node (ref "U1") (pin "2") (pinfunction "VCC_3V3_2") (pintype "bidirectional"))
    )
    (net (code "162") (name "~{RESET}") (class "Default")
      (node (ref "C101") (pin "2") (pinfunction "2_2") (pintype "passive"))
      (node (ref "C110") (pin "2") (pinfunction "2_2") (pintype "passive"))
      (node (ref "D101") (pin "A") (pinfunction "A_A") (pintype "passive"))
      (node (ref "IC101") (pin "30") (pinfunction "RESET_30") (pintype "input"))
      (node (ref "J101") (pin "5") (pinfunction "5_5") (pintype "passive"))
      (node (ref "R101") (pin "1") (pinfunction "1_1") (pintype "passive"))
    )
  )
)
